# NixiTubeClock.net
KiCad netlist of a schematic drawn in EAGLE
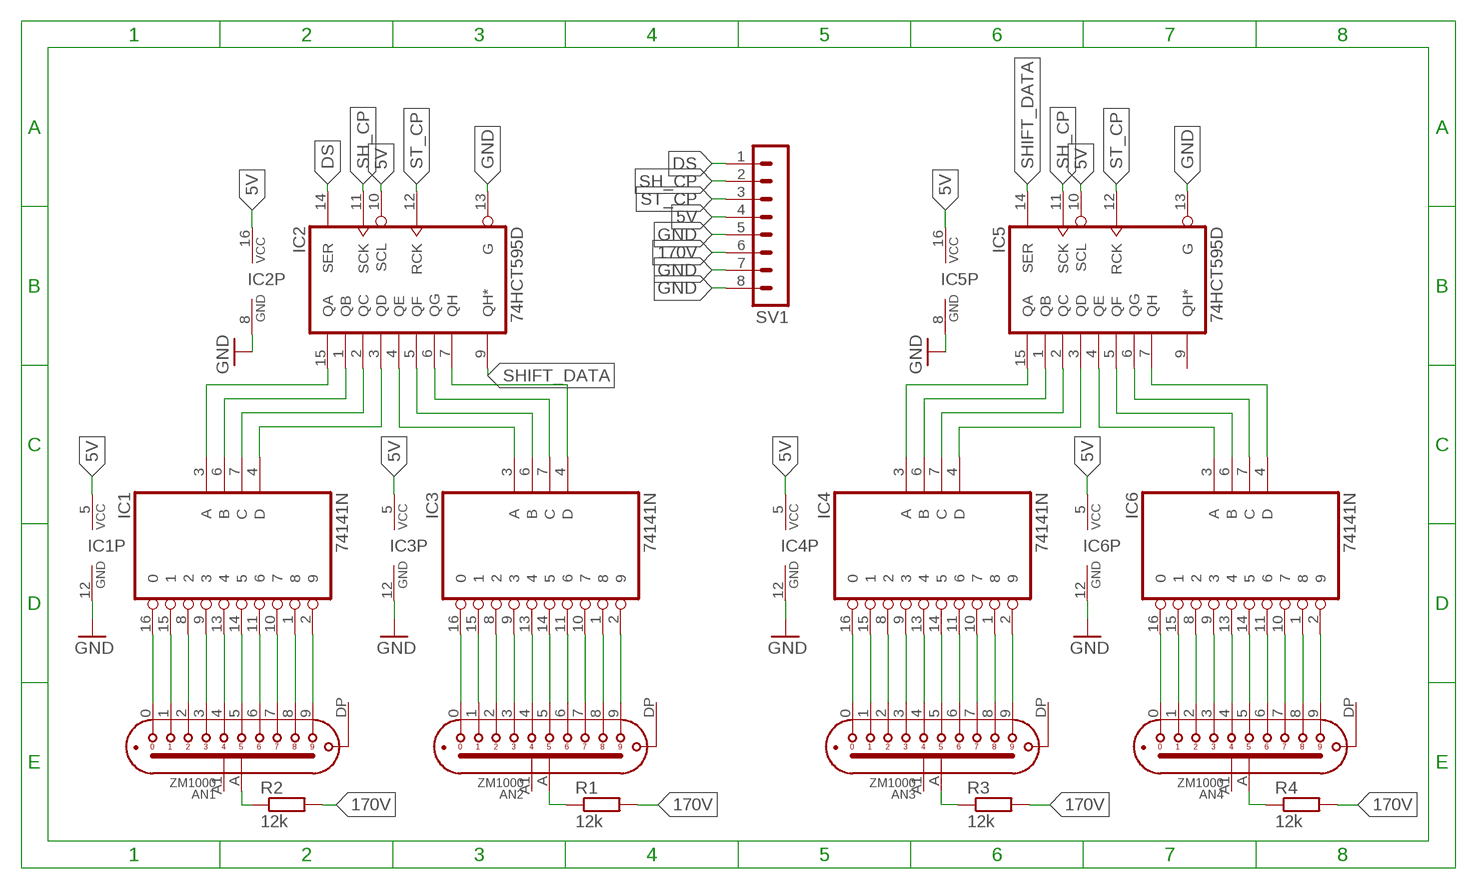
[diagram p0: schematic, sheet 1]
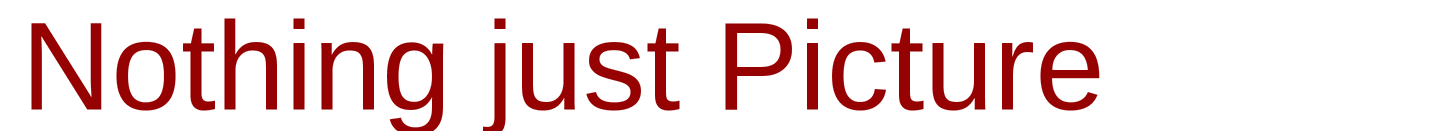
[diagram p1: schematic, sheet 2]

(export (version "E")
  (design (tool "Eeschema 10.0.6"))
  (components
    (comp (ref "AN1")
      (value "ZM1000")
      (footprint "eagle-import:ZM1000")
      (libsource (lib "eagle-import") (part "ZM1000"))
    )
    (comp (ref "AN2")
      (value "ZM1000")
      (footprint "eagle-import:ZM1000")
      (libsource (lib "eagle-import") (part "ZM1000"))
    )
    (comp (ref "AN3")
      (value "ZM1000")
      (footprint "eagle-import:ZM1000")
      (libsource (lib "eagle-import") (part "ZM1000"))
    )
    (comp (ref "AN4")
      (value "ZM1000")
      (footprint "eagle-import:ZM1000")
      (libsource (lib "eagle-import") (part "ZM1000"))
    )
    (comp (ref "IC1")
      (value "74141N")
      (footprint "eagle-import:DIL16")
      (libsource (lib "eagle-import") (part "74141N"))
    )
    (comp (ref "IC2")
      (value "74HCT595D")
      (footprint "eagle-import:SO16")
      (libsource (lib "eagle-import") (part "74595DHCT"))
    )
    (comp (ref "IC3")
      (value "74141N")
      (footprint "eagle-import:DIL16")
      (libsource (lib "eagle-import") (part "74141N"))
    )
    (comp (ref "IC4")
      (value "74141N")
      (footprint "eagle-import:DIL16")
      (libsource (lib "eagle-import") (part "74141N"))
    )
    (comp (ref "IC5")
      (value "74HCT595D")
      (footprint "eagle-import:SO16")
      (libsource (lib "eagle-import") (part "74595DHCT"))
    )
    (comp (ref "IC6")
      (value "74141N")
      (footprint "eagle-import:DIL16")
      (libsource (lib "eagle-import") (part "74141N"))
    )
    (comp (ref "R1")
      (value "12k")
      (footprint "eagle-import:R1206")
      (libsource (lib "eagle-import") (part "R-EU_1206R1206"))
    )
    (comp (ref "R2")
      (value "12k")
      (footprint "eagle-import:R1206")
      (libsource (lib "eagle-import") (part "R-EU_1206R1206"))
    )
    (comp (ref "R3")
      (value "12k")
      (footprint "eagle-import:R1206")
      (libsource (lib "eagle-import") (part "R-EU_1206R1206"))
    )
    (comp (ref "R4")
      (value "12k")
      (footprint "eagle-import:R1206")
      (libsource (lib "eagle-import") (part "R-EU_1206R1206"))
    )
    (comp (ref "SV1")
      (value "MA08-1")
      (footprint "eagle-import:MA08-1")
      (libsource (lib "eagle-import") (part "MA08-1"))
    )
  )
  (nets
    (net (code "1") (name "5V") (class "Default")
      (node (ref "IC1") (pin "5") (pinfunction "VCC_5") (pintype "power_in"))
      (node (ref "IC2") (pin "10") (pinfunction "SCL_10") (pintype "input"))
      (node (ref "IC2") (pin "16") (pinfunction "VCC_16") (pintype "power_in"))
      (node (ref "IC3") (pin "5") (pinfunction "VCC_5") (pintype "power_in"))
      (node (ref "IC4") (pin "5") (pinfunction "VCC_5") (pintype "power_in"))
      (node (ref "IC5") (pin "10") (pinfunction "SCL_10") (pintype "input"))
      (node (ref "IC5") (pin "16") (pinfunction "VCC_16") (pintype "power_in"))
      (node (ref "IC6") (pin "5") (pinfunction "VCC_5") (pintype "power_in"))
      (node (ref "SV1") (pin "4") (pinfunction "4_4") (pintype "passive"))
    )
    (net (code "2") (name "170V") (class "Default")
      (node (ref "R1") (pin "2") (pinfunction "2_2") (pintype "passive"))
      (node (ref "R2") (pin "2") (pinfunction "2_2") (pintype "passive"))
      (node (ref "R3") (pin "2") (pinfunction "2_2") (pintype "passive"))
      (node (ref "R4") (pin "2") (pinfunction "2_2") (pintype "passive"))
      (node (ref "SV1") (pin "6") (pinfunction "6_6") (pintype "passive"))
    )
    (net (code "3") (name "DS") (class "Default")
      (node (ref "IC2") (pin "14") (pinfunction "SER_14") (pintype "input"))
      (node (ref "SV1") (pin "1") (pinfunction "1_1") (pintype "passive"))
    )
    (net (code "4") (name "GND") (class "Default")
      (node (ref "IC1") (pin "12") (pinfunction "GND_12") (pintype "power_in"))
      (node (ref "IC2") (pin "13") (pinfunction "G_13") (pintype "input"))
      (node (ref "IC2") (pin "8") (pinfunction "GND_8") (pintype "power_in"))
      (node (ref "IC3") (pin "12") (pinfunction "GND_12") (pintype "power_in"))
      (node (ref "IC4") (pin "12") (pinfunction "GND_12") (pintype "power_in"))
      (node (ref "IC5") (pin "13") (pinfunction "G_13") (pintype "input"))
      (node (ref "IC5") (pin "8") (pinfunction "GND_8") (pintype "power_in"))
      (node (ref "IC6") (pin "12") (pinfunction "GND_12") (pintype "power_in"))
      (node (ref "SV1") (pin "5") (pinfunction "5_5") (pintype "passive"))
      (node (ref "SV1") (pin "7") (pinfunction "7_7") (pintype "passive"))
      (node (ref "SV1") (pin "8") (pinfunction "8_8") (pintype "passive"))
    )
    (net (code "5") (name "Net-(AN1-A1)") (class "Default")
      (node (ref "AN1") (pin "A") (pinfunction "A1_A") (pintype "passive"))
      (node (ref "R2") (pin "1") (pinfunction "1_1") (pintype "passive"))
    )
    (net (code "6") (name "Net-(AN2-A1)") (class "Default")
      (node (ref "AN2") (pin "A") (pinfunction "A1_A") (pintype "passive"))
      (node (ref "R1") (pin "1") (pinfunction "1_1") (pintype "passive"))
    )
    (net (code "7") (name "Net-(AN3-A1)") (class "Default")
      (node (ref "AN3") (pin "A") (pinfunction "A1_A") (pintype "passive"))
      (node (ref "R3") (pin "1") (pinfunction "1_1") (pintype "passive"))
    )
    (net (code "8") (name "Net-(AN4-A1)") (class "Default")
      (node (ref "AN4") (pin "A") (pinfunction "A1_A") (pintype "passive"))
      (node (ref "R4") (pin "1") (pinfunction "1_1") (pintype "passive"))
    )
    (net (code "9") (name "Net-(IC1A-0)") (class "Default")
      (node (ref "AN1") (pin "0") (pinfunction "0_0") (pintype "passive"))
      (node (ref "IC1") (pin "16") (pinfunction "0_16") (pintype "open_collector"))
    )
    (net (code "10") (name "Net-(IC1A-1)") (class "Default")
      (node (ref "AN1") (pin "1") (pinfunction "1_1") (pintype "passive"))
      (node (ref "IC1") (pin "15") (pinfunction "1_15") (pintype "open_collector"))
    )
    (net (code "11") (name "Net-(IC1A-2)") (class "Default")
      (node (ref "AN1") (pin "2") (pinfunction "2_2") (pintype "passive"))
      (node (ref "IC1") (pin "8") (pinfunction "2_8") (pintype "open_collector"))
    )
    (net (code "12") (name "Net-(IC1A-3)") (class "Default")
      (node (ref "AN1") (pin "3") (pinfunction "3_3") (pintype "passive"))
      (node (ref "IC1") (pin "9") (pinfunction "3_9") (pintype "open_collector"))
    )
    (net (code "13") (name "Net-(IC1A-4)") (class "Default")
      (node (ref "AN1") (pin "4") (pinfunction "4_4") (pintype "passive"))
      (node (ref "IC1") (pin "13") (pinfunction "4_13") (pintype "open_collector"))
    )
    (net (code "14") (name "Net-(IC1A-5)") (class "Default")
      (node (ref "AN1") (pin "5") (pinfunction "5_5") (pintype "passive"))
      (node (ref "IC1") (pin "14") (pinfunction "5_14") (pintype "open_collector"))
    )
    (net (code "15") (name "Net-(IC1A-6)") (class "Default")
      (node (ref "AN1") (pin "6") (pinfunction "6_6") (pintype "passive"))
      (node (ref "IC1") (pin "11") (pinfunction "6_11") (pintype "open_collector"))
    )
    (net (code "16") (name "Net-(IC1A-7)") (class "Default")
      (node (ref "AN1") (pin "7") (pinfunction "7_7") (pintype "passive"))
      (node (ref "IC1") (pin "10") (pinfunction "7_10") (pintype "open_collector"))
    )
    (net (code "17") (name "Net-(IC1A-8)") (class "Default")
      (node (ref "AN1") (pin "8") (pinfunction "8_8") (pintype "passive"))
      (node (ref "IC1") (pin "1") (pinfunction "8_1") (pintype "open_collector"))
    )
    (net (code "18") (name "Net-(IC1A-9)") (class "Default")
      (node (ref "AN1") (pin "9") (pinfunction "9_9") (pintype "passive"))
      (node (ref "IC1") (pin "2") (pinfunction "9_2") (pintype "open_collector"))
    )
    (net (code "19") (name "Net-(IC1A-A)") (class "Default")
      (node (ref "IC1") (pin "3") (pinfunction "A_3") (pintype "input"))
      (node (ref "IC2") (pin "15") (pinfunction "QA_15") (pintype "tri_state"))
    )
    (net (code "20") (name "Net-(IC1A-B)") (class "Default")
      (node (ref "IC1") (pin "6") (pinfunction "B_6") (pintype "input"))
      (node (ref "IC2") (pin "1") (pinfunction "QB_1") (pintype "tri_state"))
    )
    (net (code "21") (name "Net-(IC1A-C)") (class "Default")
      (node (ref "IC1") (pin "7") (pinfunction "C_7") (pintype "input"))
      (node (ref "IC2") (pin "2") (pinfunction "QC_2") (pintype "tri_state"))
    )
    (net (code "22") (name "Net-(IC1A-D)") (class "Default")
      (node (ref "IC1") (pin "4") (pinfunction "D_4") (pintype "input"))
      (node (ref "IC2") (pin "3") (pinfunction "QD_3") (pintype "tri_state"))
    )
    (net (code "23") (name "Net-(IC2A-QE)") (class "Default")
      (node (ref "IC2") (pin "4") (pinfunction "QE_4") (pintype "tri_state"))
      (node (ref "IC3") (pin "3") (pinfunction "A_3") (pintype "input"))
    )
    (net (code "24") (name "Net-(IC2A-QF)") (class "Default")
      (node (ref "IC2") (pin "5") (pinfunction "QF_5") (pintype "tri_state"))
      (node (ref "IC3") (pin "6") (pinfunction "B_6") (pintype "input"))
    )
    (net (code "25") (name "Net-(IC2A-QG)") (class "Default")
      (node (ref "IC2") (pin "6") (pinfunction "QG_6") (pintype "tri_state"))
      (node (ref "IC3") (pin "7") (pinfunction "C_7") (pintype "input"))
    )
    (net (code "26") (name "Net-(IC2A-QH)") (class "Default")
      (node (ref "IC2") (pin "7") (pinfunction "QH_7") (pintype "tri_state"))
      (node (ref "IC3") (pin "4") (pinfunction "D_4") (pintype "input"))
    )
    (net (code "27") (name "Net-(IC3A-0)") (class "Default")
      (node (ref "AN2") (pin "0") (pinfunction "0_0") (pintype "passive"))
      (node (ref "IC3") (pin "16") (pinfunction "0_16") (pintype "open_collector"))
    )
    (net (code "28") (name "Net-(IC3A-1)") (class "Default")
      (node (ref "AN2") (pin "1") (pinfunction "1_1") (pintype "passive"))
      (node (ref "IC3") (pin "15") (pinfunction "1_15") (pintype "open_collector"))
    )
    (net (code "29") (name "Net-(IC3A-2)") (class "Default")
      (node (ref "AN2") (pin "2") (pinfunction "2_2") (pintype "passive"))
      (node (ref "IC3") (pin "8") (pinfunction "2_8") (pintype "open_collector"))
    )
    (net (code "30") (name "Net-(IC3A-3)") (class "Default")
      (node (ref "AN2") (pin "3") (pinfunction "3_3") (pintype "passive"))
      (node (ref "IC3") (pin "9") (pinfunction "3_9") (pintype "open_collector"))
    )
    (net (code "31") (name "Net-(IC3A-4)") (class "Default")
      (node (ref "AN2") (pin "4") (pinfunction "4_4") (pintype "passive"))
      (node (ref "IC3") (pin "13") (pinfunction "4_13") (pintype "open_collector"))
    )
    (net (code "32") (name "Net-(IC3A-5)") (class "Default")
      (node (ref "AN2") (pin "5") (pinfunction "5_5") (pintype "passive"))
      (node (ref "IC3") (pin "14") (pinfunction "5_14") (pintype "open_collector"))
    )
    (net (code "33") (name "Net-(IC3A-6)") (class "Default")
      (node (ref "AN2") (pin "6") (pinfunction "6_6") (pintype "passive"))
      (node (ref "IC3") (pin "11") (pinfunction "6_11") (pintype "open_collector"))
    )
    (net (code "34") (name "Net-(IC3A-7)") (class "Default")
      (node (ref "AN2") (pin "7") (pinfunction "7_7") (pintype "passive"))
      (node (ref "IC3") (pin "10") (pinfunction "7_10") (pintype "open_collector"))
    )
    (net (code "35") (name "Net-(IC3A-8)") (class "Default")
      (node (ref "AN2") (pin "8") (pinfunction "8_8") (pintype "passive"))
      (node (ref "IC3") (pin "1") (pinfunction "8_1") (pintype "open_collector"))
    )
    (net (code "36") (name "Net-(IC3A-9)") (class "Default")
      (node (ref "AN2") (pin "9") (pinfunction "9_9") (pintype "passive"))
      (node (ref "IC3") (pin "2") (pinfunction "9_2") (pintype "open_collector"))
    )
    (net (code "37") (name "Net-(IC4A-0)") (class "Default")
      (node (ref "AN3") (pin "0") (pinfunction "0_0") (pintype "passive"))
      (node (ref "IC4") (pin "16") (pinfunction "0_16") (pintype "open_collector"))
    )
    (net (code "38") (name "Net-(IC4A-1)") (class "Default")
      (node (ref "AN3") (pin "1") (pinfunction "1_1") (pintype "passive"))
      (node (ref "IC4") (pin "15") (pinfunction "1_15") (pintype "open_collector"))
    )
    (net (code "39") (name "Net-(IC4A-2)") (class "Default")
      (node (ref "AN3") (pin "2") (pinfunction "2_2") (pintype "passive"))
      (node (ref "IC4") (pin "8") (pinfunction "2_8") (pintype "open_collector"))
    )
    (net (code "40") (name "Net-(IC4A-3)") (class "Default")
      (node (ref "AN3") (pin "3") (pinfunction "3_3") (pintype "passive"))
      (node (ref "IC4") (pin "9") (pinfunction "3_9") (pintype "open_collector"))
    )
    (net (code "41") (name "Net-(IC4A-4)") (class "Default")
      (node (ref "AN3") (pin "4") (pinfunction "4_4") (pintype "passive"))
      (node (ref "IC4") (pin "13") (pinfunction "4_13") (pintype "open_collector"))
    )
    (net (code "42") (name "Net-(IC4A-5)") (class "Default")
      (node (ref "AN3") (pin "5") (pinfunction "5_5") (pintype "passive"))
      (node (ref "IC4") (pin "14") (pinfunction "5_14") (pintype "open_collector"))
    )
    (net (code "43") (name "Net-(IC4A-6)") (class "Default")
      (node (ref "AN3") (pin "6") (pinfunction "6_6") (pintype "passive"))
      (node (ref "IC4") (pin "11") (pinfunction "6_11") (pintype "open_collector"))
    )
    (net (code "44") (name "Net-(IC4A-7)") (class "Default")
      (node (ref "AN3") (pin "7") (pinfunction "7_7") (pintype "passive"))
      (node (ref "IC4") (pin "10") (pinfunction "7_10") (pintype "open_collector"))
    )
    (net (code "45") (name "Net-(IC4A-8)") (class "Default")
      (node (ref "AN3") (pin "8") (pinfunction "8_8") (pintype "passive"))
      (node (ref "IC4") (pin "1") (pinfunction "8_1") (pintype "open_collector"))
    )
    (net (code "46") (name "Net-(IC4A-9)") (class "Default")
      (node (ref "AN3") (pin "9") (pinfunction "9_9") (pintype "passive"))
      (node (ref "IC4") (pin "2") (pinfunction "9_2") (pintype "open_collector"))
    )
    (net (code "47") (name "Net-(IC4A-A)") (class "Default")
      (node (ref "IC4") (pin "3") (pinfunction "A_3") (pintype "input"))
      (node (ref "IC5") (pin "15") (pinfunction "QA_15") (pintype "tri_state"))
    )
    (net (code "48") (name "Net-(IC4A-B)") (class "Default")
      (node (ref "IC4") (pin "6") (pinfunction "B_6") (pintype "input"))
      (node (ref "IC5") (pin "1") (pinfunction "QB_1") (pintype "tri_state"))
    )
    (net (code "49") (name "Net-(IC4A-C)") (class "Default")
      (node (ref "IC4") (pin "7") (pinfunction "C_7") (pintype "input"))
      (node (ref "IC5") (pin "2") (pinfunction "QC_2") (pintype "tri_state"))
    )
    (net (code "50") (name "Net-(IC4A-D)") (class "Default")
      (node (ref "IC4") (pin "4") (pinfunction "D_4") (pintype "input"))
      (node (ref "IC5") (pin "3") (pinfunction "QD_3") (pintype "tri_state"))
    )
    (net (code "51") (name "Net-(IC5A-QE)") (class "Default")
      (node (ref "IC5") (pin "4") (pinfunction "QE_4") (pintype "tri_state"))
      (node (ref "IC6") (pin "3") (pinfunction "A_3") (pintype "input"))
    )
    (net (code "52") (name "Net-(IC5A-QF)") (class "Default")
      (node (ref "IC5") (pin "5") (pinfunction "QF_5") (pintype "tri_state"))
      (node (ref "IC6") (pin "6") (pinfunction "B_6") (pintype "input"))
    )
    (net (code "53") (name "Net-(IC5A-QG)") (class "Default")
      (node (ref "IC5") (pin "6") (pinfunction "QG_6") (pintype "tri_state"))
      (node (ref "IC6") (pin "7") (pinfunction "C_7") (pintype "input"))
    )
    (net (code "54") (name "Net-(IC5A-QH)") (class "Default")
      (node (ref "IC5") (pin "7") (pinfunction "QH_7") (pintype "tri_state"))
      (node (ref "IC6") (pin "4") (pinfunction "D_4") (pintype "input"))
    )
    (net (code "55") (name "Net-(IC6A-0)") (class "Default")
      (node (ref "AN4") (pin "0") (pinfunction "0_0") (pintype "passive"))
      (node (ref "IC6") (pin "16") (pinfunction "0_16") (pintype "open_collector"))
    )
    (net (code "56") (name "Net-(IC6A-1)") (class "Default")
      (node (ref "AN4") (pin "1") (pinfunction "1_1") (pintype "passive"))
      (node (ref "IC6") (pin "15") (pinfunction "1_15") (pintype "open_collector"))
    )
    (net (code "57") (name "Net-(IC6A-2)") (class "Default")
      (node (ref "AN4") (pin "2") (pinfunction "2_2") (pintype "passive"))
      (node (ref "IC6") (pin "8") (pinfunction "2_8") (pintype "open_collector"))
    )
    (net (code "58") (name "Net-(IC6A-3)") (class "Default")
      (node (ref "AN4") (pin "3") (pinfunction "3_3") (pintype "passive"))
      (node (ref "IC6") (pin "9") (pinfunction "3_9") (pintype "open_collector"))
    )
    (net (code "59") (name "Net-(IC6A-4)") (class "Default")
      (node (ref "AN4") (pin "4") (pinfunction "4_4") (pintype "passive"))
      (node (ref "IC6") (pin "13") (pinfunction "4_13") (pintype "open_collector"))
    )
    (net (code "60") (name "Net-(IC6A-5)") (class "Default")
      (node (ref "AN4") (pin "5") (pinfunction "5_5") (pintype "passive"))
      (node (ref "IC6") (pin "14") (pinfunction "5_14") (pintype "open_collector"))
    )
    (net (code "61") (name "Net-(IC6A-6)") (class "Default")
      (node (ref "AN4") (pin "6") (pinfunction "6_6") (pintype "passive"))
      (node (ref "IC6") (pin "11") (pinfunction "6_11") (pintype "open_collector"))
    )
    (net (code "62") (name "Net-(IC6A-7)") (class "Default")
      (node (ref "AN4") (pin "7") (pinfunction "7_7") (pintype "passive"))
      (node (ref "IC6") (pin "10") (pinfunction "7_10") (pintype "open_collector"))
    )
    (net (code "63") (name "Net-(IC6A-8)") (class "Default")
      (node (ref "AN4") (pin "8") (pinfunction "8_8") (pintype "passive"))
      (node (ref "IC6") (pin "1") (pinfunction "8_1") (pintype "open_collector"))
    )
    (net (code "64") (name "Net-(IC6A-9)") (class "Default")
      (node (ref "AN4") (pin "9") (pinfunction "9_9") (pintype "passive"))
      (node (ref "IC6") (pin "2") (pinfunction "9_2") (pintype "open_collector"))
    )
    (net (code "65") (name "SHIFT_DATA") (class "Default")
      (node (ref "IC2") (pin "9") (pinfunction "QH*_9") (pintype "tri_state"))
      (node (ref "IC5") (pin "14") (pinfunction "SER_14") (pintype "input"))
    )
    (net (code "66") (name "SH_CP") (class "Default")
      (node (ref "IC2") (pin "11") (pinfunction "SCK_11") (pintype "input"))
      (node (ref "IC5") (pin "11") (pinfunction "SCK_11") (pintype "input"))
      (node (ref "SV1") (pin "2") (pinfunction "2_2") (pintype "passive"))
    )
    (net (code "67") (name "ST_CP") (class "Default")
      (node (ref "IC2") (pin "12") (pinfunction "RCK_12") (pintype "input"))
      (node (ref "IC5") (pin "12") (pinfunction "RCK_12") (pintype "input"))
      (node (ref "SV1") (pin "3") (pinfunction "3_3") (pintype "passive"))
    )
    (net (code "68") (name "unconnected-(AN1-A2-PadA1)") (class "Default")
      (node (ref "AN1") (pin "A1") (pinfunction "A2_A1") (pintype "passive"))
    )
    (net (code "69") (name "unconnected-(AN1-DPL-PadDP)") (class "Default")
      (node (ref "AN1") (pin "DP") (pinfunction "DPL_DP") (pintype "passive"))
    )
    (net (code "70") (name "unconnected-(AN2-A2-PadA1)") (class "Default")
      (node (ref "AN2") (pin "A1") (pinfunction "A2_A1") (pintype "passive"))
    )
    (net (code "71") (name "unconnected-(AN2-DPL-PadDP)") (class "Default")
      (node (ref "AN2") (pin "DP") (pinfunction "DPL_DP") (pintype "passive"))
    )
    (net (code "72") (name "unconnected-(AN3-A2-PadA1)") (class "Default")
      (node (ref "AN3") (pin "A1") (pinfunction "A2_A1") (pintype "passive"))
    )
    (net (code "73") (name "unconnected-(AN3-DPL-PadDP)") (class "Default")
      (node (ref "AN3") (pin "DP") (pinfunction "DPL_DP") (pintype "passive"))
    )
    (net (code "74") (name "unconnected-(AN4-A2-PadA1)") (class "Default")
      (node (ref "AN4") (pin "A1") (pinfunction "A2_A1") (pintype "passive"))
    )
    (net (code "75") (name "unconnected-(AN4-DPL-PadDP)") (class "Default")
      (node (ref "AN4") (pin "DP") (pinfunction "DPL_DP") (pintype "passive"))
    )
    (net (code "76") (name "unconnected-(IC5A-QH*-Pad9)") (class "Default")
      (node (ref "IC5") (pin "9") (pinfunction "QH*_9") (pintype "tri_state"))
    )
  )
)
